# BLDC_v3_p2.net
KiCad netlist of a schematic drawn in Altium Designer
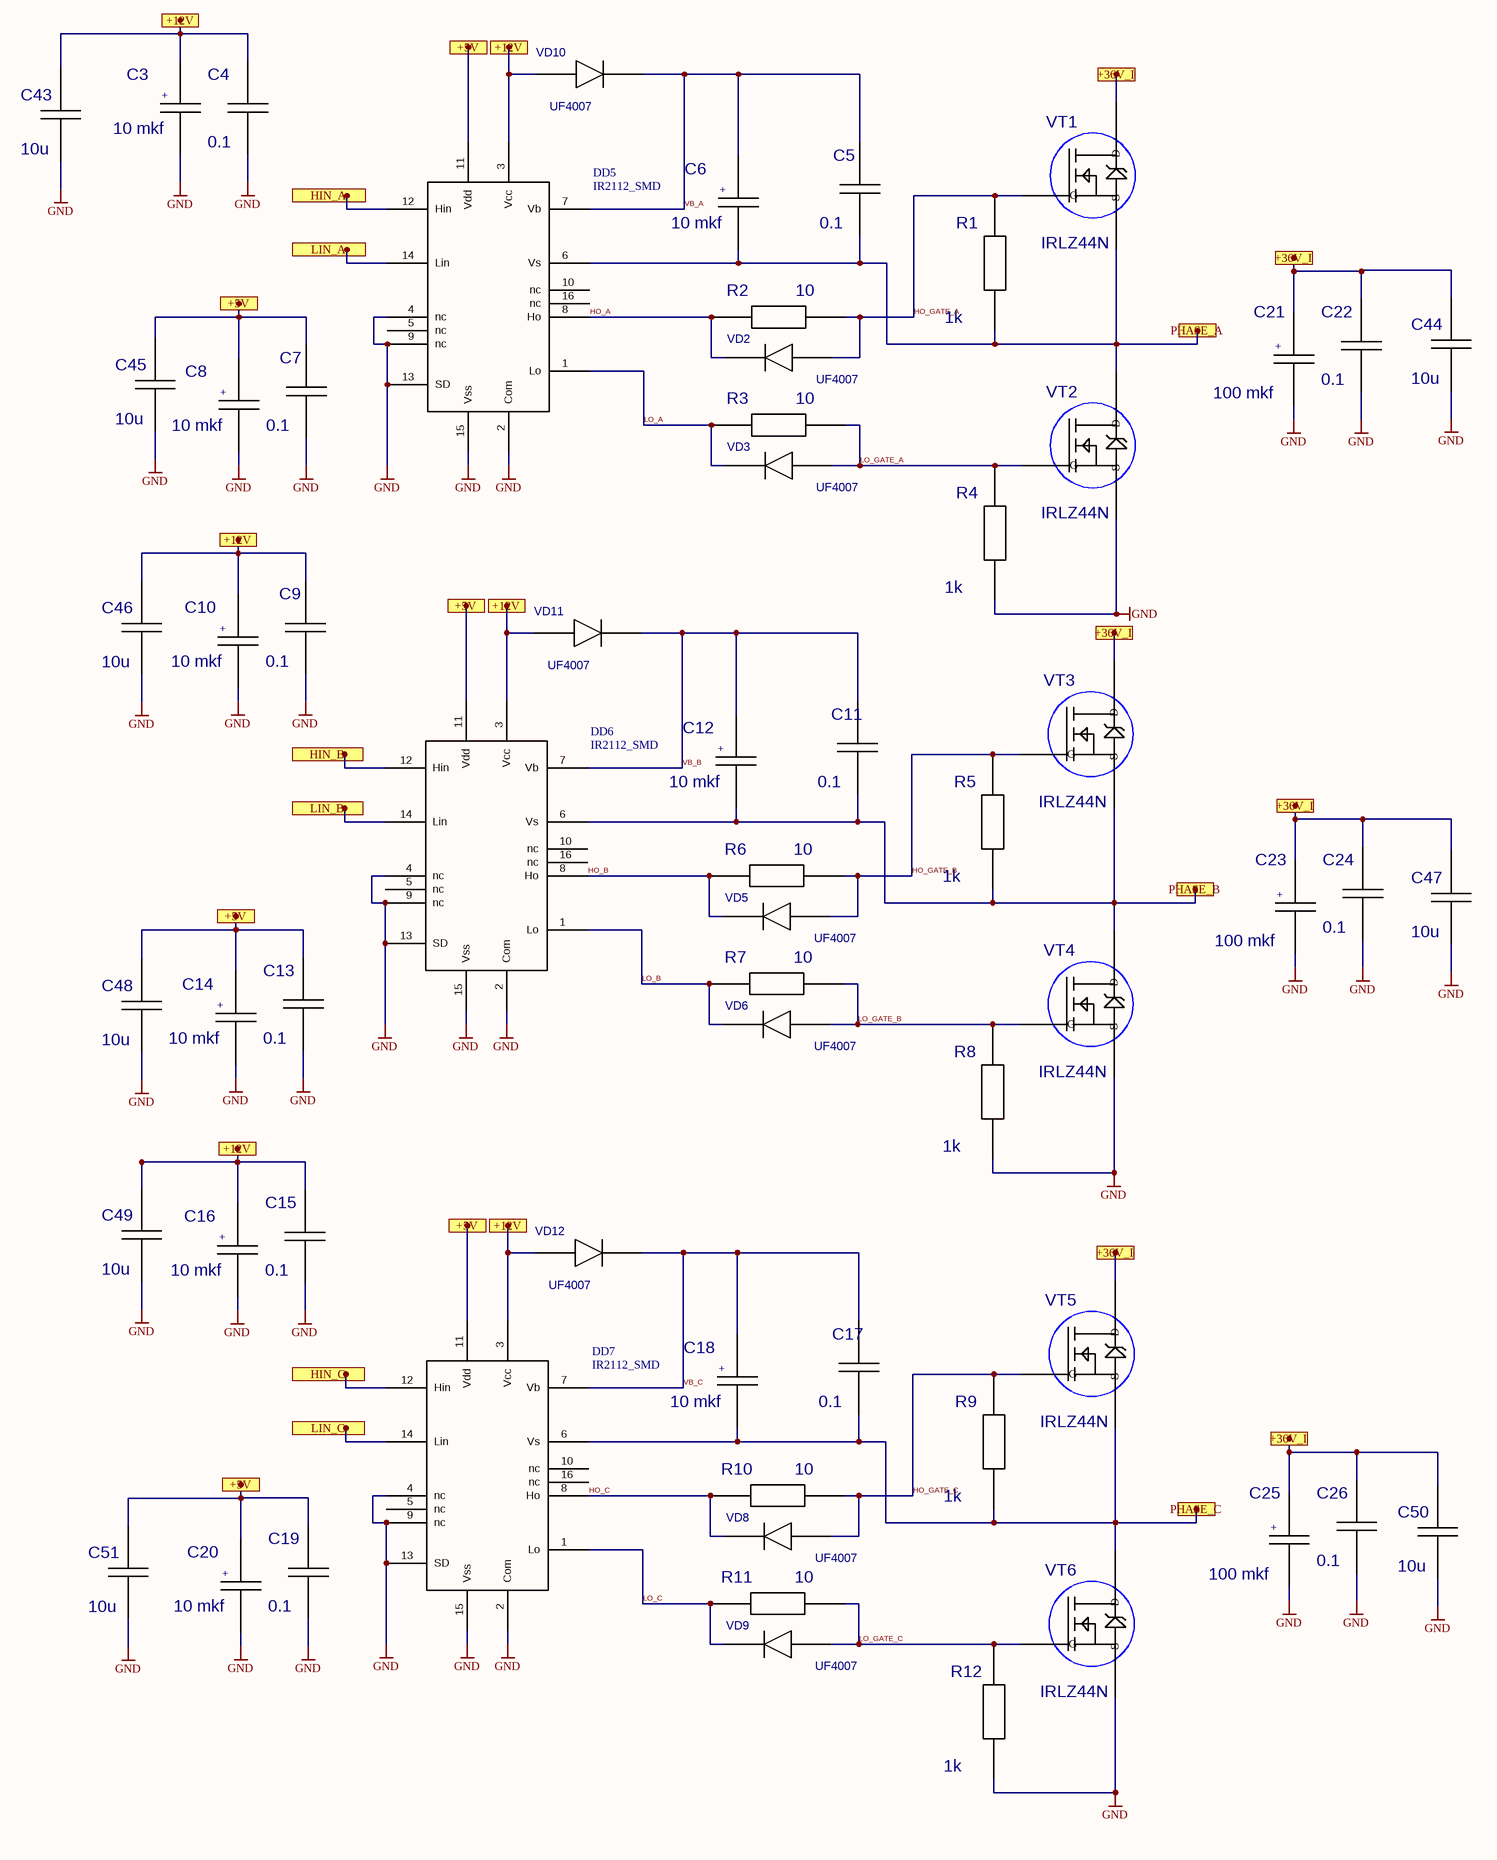
[diagram p0: BLDC_v3_p2.SCHDOC]

(export (version "E")
  (design (tool "Eeschema 10.0.6"))
  (components
    (comp (ref "C3")
      (value "10 mkf")
      (footprint "C10_V")
      (description "C10_V")
      (libsource (lib "") (part "C10_V_3"))
    )
    (comp (ref "C4")
      (value "0.1")
      (footprint "RC1206")
      (description "C_1206")
      (libsource (lib "*") (part "C_1206"))
    )
    (comp (ref "C5")
      (value "0.1")
      (footprint "RC1206")
      (description "C_1206")
      (libsource (lib "") (part "C_1206_1"))
    )
    (comp (ref "C6")
      (value "10 mkf")
      (footprint "C10_V")
      (description "C10_V")
      (libsource (lib "*") (part "C10_V"))
    )
    (comp (ref "C7")
      (value "0.1")
      (footprint "RC1206")
      (description "C_1206")
      (libsource (lib "") (part "C_1206_3"))
    )
    (comp (ref "C8")
      (value "10 mkf")
      (footprint "C10_V")
      (description "C10_V")
      (libsource (lib "") (part "C10_V_4"))
    )
    (comp (ref "C9")
      (value "0.1")
      (footprint "RC1206")
      (description "C_1206")
      (libsource (lib "*") (part "C_1206"))
    )
    (comp (ref "C10")
      (value "10 mkf")
      (footprint "C10_V")
      (description "C10_V")
      (libsource (lib "") (part "C10_V_3"))
    )
    (comp (ref "C11")
      (value "0.1")
      (footprint "RC1206")
      (description "C_1206")
      (libsource (lib "") (part "C_1206_1"))
    )
    (comp (ref "C12")
      (value "10 mkf")
      (footprint "C10_V")
      (description "C10_V")
      (libsource (lib "") (part "C10_V_1"))
    )
    (comp (ref "C13")
      (value "0.1")
      (footprint "RC1206")
      (description "C_1206")
      (libsource (lib "") (part "C_1206_1"))
    )
    (comp (ref "C14")
      (value "10 mkf")
      (footprint "C10_V")
      (description "C10_V")
      (libsource (lib "") (part "C10_V_1"))
    )
    (comp (ref "C15")
      (value "0.1")
      (footprint "RC1206")
      (description "C_1206")
      (libsource (lib "") (part "C_1206_1"))
    )
    (comp (ref "C16")
      (value "10 mkf")
      (footprint "C10_V")
      (description "C10_V")
      (libsource (lib "") (part "C10_V_1"))
    )
    (comp (ref "C17")
      (value "0.1")
      (footprint "RC1206")
      (description "C_1206")
      (libsource (lib "") (part "C_1206_2"))
    )
    (comp (ref "C18")
      (value "10 mkf")
      (footprint "C10_V")
      (description "C10_V")
      (libsource (lib "") (part "C10_V_2"))
    )
    (comp (ref "C19")
      (value "0.1")
      (footprint "RC1206")
      (description "C_1206")
      (libsource (lib "*") (part "C_1206"))
    )
    (comp (ref "C20")
      (value "10 mkf")
      (footprint "C10_V")
      (description "C10_V")
      (libsource (lib "") (part "C10_V_3"))
    )
    (comp (ref "C21")
      (value "100 mkf")
      (footprint "C100_WIDE")
      (description "C100_V_WIDE")
      (libsource (lib "*") (part "C100_V_WIDE"))
    )
    (comp (ref "C22")
      (value "0.1")
      (footprint "RC1206")
      (description "C_1206")
      (libsource (lib "*") (part "C_1206"))
    )
    (comp (ref "C23")
      (value "100 mkf")
      (footprint "C100_WIDE")
      (description "C100_V_WIDE")
      (libsource (lib "*") (part "C100_V_WIDE"))
    )
    (comp (ref "C24")
      (value "0.1")
      (footprint "RC1206")
      (description "C_1206")
      (libsource (lib "*") (part "C_1206"))
    )
    (comp (ref "C25")
      (value "100 mkf")
      (footprint "C100_WIDE")
      (description "C100_V_WIDE")
      (libsource (lib "") (part "C100_V_WIDE_1"))
    )
    (comp (ref "C26")
      (value "0.1")
      (footprint "RC1206")
      (description "C_1206")
      (libsource (lib "") (part "C_1206_1"))
    )
    (comp (ref "C43")
      (value "10u")
      (footprint "RC1206")
      (description "C_1206")
      (libsource (lib "") (part "C_1206_1"))
    )
    (comp (ref "C44")
      (value "10u")
      (footprint "RC1206")
      (description "C_1206")
      (libsource (lib "") (part "C_1206_1"))
    )
    (comp (ref "C45")
      (value "10u")
      (footprint "RC1206")
      (description "C_1206")
      (libsource (lib "") (part "C_1206_1"))
    )
    (comp (ref "C46")
      (value "10u")
      (footprint "RC1206")
      (description "C_1206")
      (libsource (lib "") (part "C_1206_1"))
    )
    (comp (ref "C47")
      (value "10u")
      (footprint "RC1206")
      (description "C_1206")
      (libsource (lib "") (part "C_1206_1"))
    )
    (comp (ref "C48")
      (value "10u")
      (footprint "RC1206")
      (description "C_1206")
      (libsource (lib "") (part "C_1206_1"))
    )
    (comp (ref "C49")
      (value "10u")
      (footprint "RC1206")
      (description "C_1206")
      (libsource (lib "") (part "C_1206_1"))
    )
    (comp (ref "C50")
      (value "10u")
      (footprint "RC1206")
      (description "C_1206")
      (libsource (lib "") (part "C_1206_1"))
    )
    (comp (ref "C51")
      (value "10u")
      (footprint "RC1206")
      (description "C_1206")
      (libsource (lib "") (part "C_1206_1"))
    )
    (comp (ref "DD5")
      (value "IR2112_SMD")
      (footprint "SOIC16_N")
      (description "High and Low Side Driver")
      (fields (field (name "PUBLISHER") "Altium Limited"))
      (libsource (lib "bldc") (part "IR2112_SMD"))
    )
    (comp (ref "DD6")
      (value "IR2112_SMD")
      (footprint "SOIC16_N")
      (description "High and Low Side Driver")
      (fields (field (name "PUBLISHER") "Altium Limited"))
      (libsource (lib "bldc") (part "IR2112_SMD"))
    )
    (comp (ref "DD7")
      (value "IR2112_SMD")
      (footprint "SOIC16_N")
      (description "High and Low Side Driver")
      (fields (field (name "PUBLISHER") "Altium Limited"))
      (libsource (lib "bldc") (part "IR2112_SMD"))
    )
    (comp (ref "R1")
      (value "1k")
      (footprint "CC1206")
      (description "R_1206")
      (libsource (lib "") (part "R_1206_1"))
    )
    (comp (ref "R2")
      (value "10")
      (footprint "CC1206")
      (description "R_1206")
      (libsource (lib "*") (part "R_1206"))
    )
    (comp (ref "R3")
      (value "10")
      (footprint "CC1206")
      (description "R_1206")
      (libsource (lib "") (part "R_1206_2"))
    )
    (comp (ref "R4")
      (value "1k")
      (footprint "CC1206")
      (description "R_1206")
      (libsource (lib "") (part "R_1206_1"))
    )
    (comp (ref "R5")
      (value "1k")
      (footprint "CC1206")
      (description "R_1206")
      (libsource (lib "") (part "R_1206_2"))
    )
    (comp (ref "R6")
      (value "10")
      (footprint "CC1206")
      (description "R_1206")
      (libsource (lib "") (part "R_1206_1"))
    )
    (comp (ref "R7")
      (value "10")
      (footprint "CC1206")
      (description "R_1206")
      (libsource (lib "") (part "R_1206_1"))
    )
    (comp (ref "R8")
      (value "1k")
      (footprint "CC1206")
      (description "R_1206")
      (libsource (lib "") (part "R_1206_2"))
    )
    (comp (ref "R9")
      (value "1k")
      (footprint "CC1206")
      (description "R_1206")
      (libsource (lib "") (part "R_1206_1"))
    )
    (comp (ref "R10")
      (value "10")
      (footprint "CC1206")
      (description "R_1206")
      (libsource (lib "") (part "R_1206_2"))
    )
    (comp (ref "R11")
      (value "10")
      (footprint "CC1206")
      (description "R_1206")
      (libsource (lib "") (part "R_1206_2"))
    )
    (comp (ref "R12")
      (value "1k")
      (footprint "CC1206")
      (description "R_1206")
      (libsource (lib "") (part "R_1206_1"))
    )
    (comp (ref "VD2")
      (value "UF4007")
      (footprint "DIODE_V_WIDE_HOLES")
      (description "DIODE_LIE_WIDE")
      (libsource (lib "*") (part "DIODE_LIE_WIDE"))
    )
    (comp (ref "VD3")
      (value "UF4007")
      (footprint "DIODE_V_WIDE_HOLES")
      (description "DIODE_LIE_WIDE")
      (libsource (lib "*") (part "DIODE_LIE_WIDE"))
    )
    (comp (ref "VD5")
      (value "UF4007")
      (footprint "DIODE_V_WIDE_HOLES")
      (description "DIODE_LIE_WIDE")
      (libsource (lib "*") (part "DIODE_LIE_WIDE"))
    )
    (comp (ref "VD6")
      (value "UF4007")
      (footprint "DIODE_V_WIDE_HOLES")
      (description "DIODE_LIE_WIDE")
      (libsource (lib "*") (part "DIODE_LIE_WIDE"))
    )
    (comp (ref "VD8")
      (value "UF4007")
      (footprint "DIODE_V_WIDE_HOLES")
      (description "DIODE_LIE_WIDE")
      (libsource (lib "*") (part "DIODE_LIE_WIDE"))
    )
    (comp (ref "VD9")
      (value "UF4007")
      (footprint "DIODE_V_WIDE_HOLES")
      (description "DIODE_LIE_WIDE")
      (libsource (lib "*") (part "DIODE_LIE_WIDE"))
    )
    (comp (ref "VD10")
      (value "UF4007")
      (footprint "DIODE_V_WIDE_HOLES")
      (description "DIODE_LIE_WIDE")
      (libsource (lib "*") (part "DIODE_LIE_WIDE"))
    )
    (comp (ref "VD11")
      (value "UF4007")
      (footprint "DIODE_V_WIDE_HOLES")
      (description "DIODE_LIE_WIDE")
      (libsource (lib "*") (part "DIODE_LIE_WIDE"))
    )
    (comp (ref "VD12")
      (value "UF4007")
      (footprint "DIODE_V_WIDE_HOLES")
      (description "DIODE_LIE_WIDE")
      (libsource (lib "*") (part "DIODE_LIE_WIDE"))
    )
    (comp (ref "VT1") (value "IRLZ44N") (footprint "IRLZ44N") (libsource (lib "") (part "IRLZ44N_1")))
    (comp (ref "VT2") (value "IRLZ44N") (footprint "IRLZ44N") (libsource (lib "") (part "IRLZ44N_1")))
    (comp (ref "VT3") (value "IRLZ44N") (footprint "IRLZ44N") (libsource (lib "*") (part "IRLZ44N")))
    (comp (ref "VT4") (value "IRLZ44N") (footprint "IRLZ44N") (libsource (lib "") (part "IRLZ44N_2")))
    (comp (ref "VT5") (value "IRLZ44N") (footprint "IRLZ44N") (libsource (lib "") (part "IRLZ44N_1")))
    (comp (ref "VT6") (value "IRLZ44N") (footprint "IRLZ44N") (libsource (lib "") (part "IRLZ44N_3")))
  )
  (nets
    (net (code "7") (name "/HO_A") (class "Default")
      (node (ref "DD5") (pin "8") (pinfunction "Ho_8") (pintype "passive"))
      (node (ref "R2") (pin "1") (pinfunction "A1_1") (pintype "passive"))
      (node (ref "VD2") (pin "2") (pinfunction "A_2") (pintype "passive"))
    )
    (net (code "8") (name "/HO_B") (class "Default")
      (node (ref "DD6") (pin "8") (pinfunction "Ho_8") (pintype "passive"))
      (node (ref "R6") (pin "1") (pinfunction "A1_1") (pintype "passive"))
      (node (ref "VD5") (pin "2") (pinfunction "A_2") (pintype "passive"))
    )
    (net (code "9") (name "/HO_C") (class "Default")
      (node (ref "DD7") (pin "8") (pinfunction "Ho_8") (pintype "passive"))
      (node (ref "R10") (pin "1") (pinfunction "A1_1") (pintype "passive"))
      (node (ref "VD8") (pin "2") (pinfunction "A_2") (pintype "passive"))
    )
    (net (code "10") (name "/HO_GATE_A") (class "Default")
      (node (ref "R1") (pin "1") (pinfunction "A1_1") (pintype "passive"))
      (node (ref "R2") (pin "2") (pinfunction "A2_2") (pintype "passive"))
      (node (ref "VD2") (pin "1") (pinfunction "C_1") (pintype "passive"))
      (node (ref "VT1") (pin "1") (pinfunction "G_1") (pintype "passive"))
    )
    (net (code "11") (name "/HO_GATE_B") (class "Default")
      (node (ref "R5") (pin "1") (pinfunction "A1_1") (pintype "passive"))
      (node (ref "R6") (pin "2") (pinfunction "A2_2") (pintype "passive"))
      (node (ref "VD5") (pin "1") (pinfunction "C_1") (pintype "passive"))
      (node (ref "VT3") (pin "1") (pinfunction "G_1") (pintype "passive"))
    )
    (net (code "12") (name "/HO_GATE_C") (class "Default")
      (node (ref "R10") (pin "2") (pinfunction "A2_2") (pintype "passive"))
      (node (ref "R9") (pin "1") (pinfunction "A1_1") (pintype "passive"))
      (node (ref "VD8") (pin "1") (pinfunction "C_1") (pintype "passive"))
      (node (ref "VT5") (pin "1") (pinfunction "G_1") (pintype "passive"))
    )
    (net (code "16") (name "/LO_A") (class "Default")
      (node (ref "DD5") (pin "1") (pinfunction "Lo_1") (pintype "passive"))
      (node (ref "R3") (pin "1") (pinfunction "A1_1") (pintype "passive"))
      (node (ref "VD3") (pin "2") (pinfunction "A_2") (pintype "passive"))
    )
    (net (code "17") (name "/LO_B") (class "Default")
      (node (ref "DD6") (pin "1") (pinfunction "Lo_1") (pintype "passive"))
      (node (ref "R7") (pin "1") (pinfunction "A1_1") (pintype "passive"))
      (node (ref "VD6") (pin "2") (pinfunction "A_2") (pintype "passive"))
    )
    (net (code "18") (name "/LO_C") (class "Default")
      (node (ref "DD7") (pin "1") (pinfunction "Lo_1") (pintype "passive"))
      (node (ref "R11") (pin "1") (pinfunction "A1_1") (pintype "passive"))
      (node (ref "VD9") (pin "2") (pinfunction "A_2") (pintype "passive"))
    )
    (net (code "19") (name "/LO_GATE_A") (class "Default")
      (node (ref "R3") (pin "2") (pinfunction "A2_2") (pintype "passive"))
      (node (ref "R4") (pin "1") (pinfunction "A1_1") (pintype "passive"))
      (node (ref "VD3") (pin "1") (pinfunction "C_1") (pintype "passive"))
      (node (ref "VT2") (pin "1") (pinfunction "G_1") (pintype "passive"))
    )
    (net (code "20") (name "/LO_GATE_B") (class "Default")
      (node (ref "R7") (pin "2") (pinfunction "A2_2") (pintype "passive"))
      (node (ref "R8") (pin "1") (pinfunction "A1_1") (pintype "passive"))
      (node (ref "VD6") (pin "1") (pinfunction "C_1") (pintype "passive"))
      (node (ref "VT4") (pin "1") (pinfunction "G_1") (pintype "passive"))
    )
    (net (code "21") (name "/LO_GATE_C") (class "Default")
      (node (ref "R11") (pin "2") (pinfunction "A2_2") (pintype "passive"))
      (node (ref "R12") (pin "1") (pinfunction "A1_1") (pintype "passive"))
      (node (ref "VD9") (pin "1") (pinfunction "C_1") (pintype "passive"))
      (node (ref "VT6") (pin "1") (pinfunction "G_1") (pintype "passive"))
    )
    (net (code "25") (name "/VB_A") (class "Default")
      (node (ref "C5") (pin "2") (pinfunction "A2_2") (pintype "passive"))
      (node (ref "C6") (pin "1") (pinfunction "A2_1") (pintype "passive"))
      (node (ref "DD5") (pin "7") (pinfunction "Vb_7") (pintype "passive"))
      (node (ref "VD10") (pin "2") (pinfunction "A_2") (pintype "passive"))
    )
    (net (code "26") (name "/VB_B") (class "Default")
      (node (ref "C11") (pin "2") (pinfunction "A2_2") (pintype "passive"))
      (node (ref "C12") (pin "1") (pinfunction "A2_1") (pintype "passive"))
      (node (ref "DD6") (pin "7") (pinfunction "Vb_7") (pintype "passive"))
      (node (ref "VD11") (pin "2") (pinfunction "A_2") (pintype "passive"))
    )
    (net (code "27") (name "/VB_C") (class "Default")
      (node (ref "C17") (pin "2") (pinfunction "A2_2") (pintype "passive"))
      (node (ref "C18") (pin "1") (pinfunction "A2_1") (pintype "passive"))
      (node (ref "DD7") (pin "7") (pinfunction "Vb_7") (pintype "passive"))
      (node (ref "VD12") (pin "2") (pinfunction "A_2") (pintype "passive"))
    )
    (net (code "28") (name "GND") (class "Default")
      (node (ref "C10") (pin "2") (pinfunction "A1_2") (pintype "passive"))
      (node (ref "C13") (pin "1") (pinfunction "A1_1") (pintype "passive"))
      (node (ref "C14") (pin "2") (pinfunction "A1_2") (pintype "passive"))
      (node (ref "C15") (pin "1") (pinfunction "A1_1") (pintype "passive"))
      (node (ref "C16") (pin "2") (pinfunction "A1_2") (pintype "passive"))
      (node (ref "C19") (pin "1") (pinfunction "A1_1") (pintype "passive"))
      (node (ref "C20") (pin "2") (pinfunction "A1_2") (pintype "passive"))
      (node (ref "C21") (pin "2") (pinfunction "A1_2") (pintype "passive"))
      (node (ref "C22") (pin "1") (pinfunction "A1_1") (pintype "passive"))
      (node (ref "C23") (pin "2") (pinfunction "A1_2") (pintype "passive"))
      (node (ref "C24") (pin "1") (pinfunction "A1_1") (pintype "passive"))
      (node (ref "C25") (pin "2") (pinfunction "A1_2") (pintype "passive"))
      (node (ref "C26") (pin "1") (pinfunction "A1_1") (pintype "passive"))
      (node (ref "C3") (pin "2") (pinfunction "A1_2") (pintype "passive"))
      (node (ref "C4") (pin "1") (pinfunction "A1_1") (pintype "passive"))
      (node (ref "C43") (pin "1") (pinfunction "A1_1") (pintype "passive"))
      (node (ref "C44") (pin "1") (pinfunction "A1_1") (pintype "passive"))
      (node (ref "C45") (pin "1") (pinfunction "A1_1") (pintype "passive"))
      (node (ref "C46") (pin "1") (pinfunction "A1_1") (pintype "passive"))
      (node (ref "C47") (pin "1") (pinfunction "A1_1") (pintype "passive"))
      (node (ref "C48") (pin "1") (pinfunction "A1_1") (pintype "passive"))
      (node (ref "C49") (pin "1") (pinfunction "A1_1") (pintype "passive"))
      (node (ref "C50") (pin "1") (pinfunction "A1_1") (pintype "passive"))
      (node (ref "C51") (pin "1") (pinfunction "A1_1") (pintype "passive"))
      (node (ref "C7") (pin "1") (pinfunction "A1_1") (pintype "passive"))
      (node (ref "C8") (pin "2") (pinfunction "A1_2") (pintype "passive"))
      (node (ref "C9") (pin "1") (pinfunction "A1_1") (pintype "passive"))
      (node (ref "DD5") (pin "13") (pinfunction "SD_13") (pintype "passive"))
      (node (ref "DD5") (pin "15") (pinfunction "Vss_15") (pintype "passive"))
      (node (ref "DD5") (pin "2") (pinfunction "Com_2") (pintype "passive"))
      (node (ref "DD5") (pin "4") (pinfunction "nc_4") (pintype "passive"))
      (node (ref "DD5") (pin "9") (pinfunction "nc_9") (pintype "passive"))
      (node (ref "DD6") (pin "13") (pinfunction "SD_13") (pintype "passive"))
      (node (ref "DD6") (pin "15") (pinfunction "Vss_15") (pintype "passive"))
      (node (ref "DD6") (pin "2") (pinfunction "Com_2") (pintype "passive"))
      (node (ref "DD6") (pin "4") (pinfunction "nc_4") (pintype "passive"))
      (node (ref "DD6") (pin "9") (pinfunction "nc_9") (pintype "passive"))
      (node (ref "DD7") (pin "13") (pinfunction "SD_13") (pintype "passive"))
      (node (ref "DD7") (pin "15") (pinfunction "Vss_15") (pintype "passive"))
      (node (ref "DD7") (pin "2") (pinfunction "Com_2") (pintype "passive"))
      (node (ref "DD7") (pin "4") (pinfunction "nc_4") (pintype "passive"))
      (node (ref "DD7") (pin "9") (pinfunction "nc_9") (pintype "passive"))
      (node (ref "R12") (pin "2") (pinfunction "A2_2") (pintype "passive"))
      (node (ref "R4") (pin "2") (pinfunction "A2_2") (pintype "passive"))
      (node (ref "R8") (pin "2") (pinfunction "A2_2") (pintype "passive"))
      (node (ref "VT2") (pin "3") (pinfunction "S_3") (pintype "passive"))
      (node (ref "VT4") (pin "3") (pinfunction "S_3") (pintype "passive"))
      (node (ref "VT6") (pin "3") (pinfunction "S_3") (pintype "passive"))
    )
    (net (code "29") (name "Net-(C3-A2)") (class "Default")
      (node (ref "C3") (pin "1") (pinfunction "A2_1") (pintype "passive"))
      (node (ref "C4") (pin "2") (pinfunction "A2_2") (pintype "passive"))
      (node (ref "C43") (pin "2") (pinfunction "A2_2") (pintype "passive"))
    )
    (net (code "30") (name "Net-(C5-A1)") (class "Default")
      (node (ref "C5") (pin "1") (pinfunction "A1_1") (pintype "passive"))
      (node (ref "C6") (pin "2") (pinfunction "A1_2") (pintype "passive"))
      (node (ref "DD5") (pin "6") (pinfunction "Vs_6") (pintype "passive"))
      (node (ref "R1") (pin "2") (pinfunction "A2_2") (pintype "passive"))
      (node (ref "VT1") (pin "3") (pinfunction "S_3") (pintype "passive"))
      (node (ref "VT2") (pin "2") (pinfunction "D_2") (pintype "passive"))
    )
    (net (code "31") (name "Net-(C10-A2)") (class "Default")
      (node (ref "C10") (pin "1") (pinfunction "A2_1") (pintype "passive"))
      (node (ref "C46") (pin "2") (pinfunction "A2_2") (pintype "passive"))
      (node (ref "C9") (pin "2") (pinfunction "A2_2") (pintype "passive"))
    )
    (net (code "32") (name "Net-(C11-A1)") (class "Default")
      (node (ref "C11") (pin "1") (pinfunction "A1_1") (pintype "passive"))
      (node (ref "C12") (pin "2") (pinfunction "A1_2") (pintype "passive"))
      (node (ref "DD6") (pin "6") (pinfunction "Vs_6") (pintype "passive"))
      (node (ref "R5") (pin "2") (pinfunction "A2_2") (pintype "passive"))
      (node (ref "VT3") (pin "3") (pinfunction "S_3") (pintype "passive"))
      (node (ref "VT4") (pin "2") (pinfunction "D_2") (pintype "passive"))
    )
    (net (code "33") (name "Net-(C13-A2)") (class "Default")
      (node (ref "C13") (pin "2") (pinfunction "A2_2") (pintype "passive"))
      (node (ref "C14") (pin "1") (pinfunction "A2_1") (pintype "passive"))
      (node (ref "C48") (pin "2") (pinfunction "A2_2") (pintype "passive"))
    )
    (net (code "34") (name "Net-(C15-A2)") (class "Default")
      (node (ref "C15") (pin "2") (pinfunction "A2_2") (pintype "passive"))
      (node (ref "C16") (pin "1") (pinfunction "A2_1") (pintype "passive"))
      (node (ref "C49") (pin "2") (pinfunction "A2_2") (pintype "passive"))
    )
    (net (code "35") (name "Net-(C17-A1)") (class "Default")
      (node (ref "C17") (pin "1") (pinfunction "A1_1") (pintype "passive"))
      (node (ref "C18") (pin "2") (pinfunction "A1_2") (pintype "passive"))
      (node (ref "DD7") (pin "6") (pinfunction "Vs_6") (pintype "passive"))
      (node (ref "R9") (pin "2") (pinfunction "A2_2") (pintype "passive"))
      (node (ref "VT5") (pin "3") (pinfunction "S_3") (pintype "passive"))
      (node (ref "VT6") (pin "2") (pinfunction "D_2") (pintype "passive"))
    )
    (net (code "36") (name "Net-(C19-A2)") (class "Default")
      (node (ref "C19") (pin "2") (pinfunction "A2_2") (pintype "passive"))
      (node (ref "C20") (pin "1") (pinfunction "A2_1") (pintype "passive"))
      (node (ref "C51") (pin "2") (pinfunction "A2_2") (pintype "passive"))
    )
    (net (code "37") (name "Net-(C21-A2)") (class "Default")
      (node (ref "C21") (pin "1") (pinfunction "A2_1") (pintype "passive"))
      (node (ref "C22") (pin "2") (pinfunction "A2_2") (pintype "passive"))
      (node (ref "C44") (pin "2") (pinfunction "A2_2") (pintype "passive"))
    )
    (net (code "38") (name "Net-(C23-A2)") (class "Default")
      (node (ref "C23") (pin "1") (pinfunction "A2_1") (pintype "passive"))
      (node (ref "C24") (pin "2") (pinfunction "A2_2") (pintype "passive"))
      (node (ref "C47") (pin "2") (pinfunction "A2_2") (pintype "passive"))
    )
    (net (code "39") (name "Net-(C25-A2)") (class "Default")
      (node (ref "C25") (pin "1") (pinfunction "A2_1") (pintype "passive"))
      (node (ref "C26") (pin "2") (pinfunction "A2_2") (pintype "passive"))
      (node (ref "C50") (pin "2") (pinfunction "A2_2") (pintype "passive"))
    )
    (net (code "40") (name "Net-(C45-A2)") (class "Default")
      (node (ref "C45") (pin "2") (pinfunction "A2_2") (pintype "passive"))
      (node (ref "C7") (pin "2") (pinfunction "A2_2") (pintype "passive"))
      (node (ref "C8") (pin "1") (pinfunction "A2_1") (pintype "passive"))
    )
    (net (code "41") (name "Net-(DD5-Vcc)") (class "Default")
      (node (ref "DD5") (pin "3") (pinfunction "Vcc_3") (pintype "passive"))
      (node (ref "VD10") (pin "1") (pinfunction "C_1") (pintype "passive"))
    )
    (net (code "42") (name "Net-(DD6-Vcc)") (class "Default")
      (node (ref "DD6") (pin "3") (pinfunction "Vcc_3") (pintype "passive"))
      (node (ref "VD11") (pin "1") (pinfunction "C_1") (pintype "passive"))
    )
    (net (code "43") (name "Net-(DD7-Vcc)") (class "Default")
      (node (ref "DD7") (pin "3") (pinfunction "Vcc_3") (pintype "passive"))
      (node (ref "VD12") (pin "1") (pinfunction "C_1") (pintype "passive"))
    )
    (net (code "44") (name "unconnected-(DD5-Hin-Pad12)") (class "Default")
      (node (ref "DD5") (pin "12") (pinfunction "Hin_12") (pintype "passive"))
    )
    (net (code "45") (name "unconnected-(DD5-Lin-Pad14)") (class "Default")
      (node (ref "DD5") (pin "14") (pinfunction "Lin_14") (pintype "passive"))
    )
    (net (code "46") (name "unconnected-(DD5-Vdd-Pad11)") (class "Default")
      (node (ref "DD5") (pin "11") (pinfunction "Vdd_11") (pintype "passive"))
    )
    (net (code "47") (name "unconnected-(DD5-nc-Pad5)") (class "Default")
      (node (ref "DD5") (pin "5") (pinfunction "nc_5") (pintype "passive"))
    )
    (net (code "48") (name "unconnected-(DD5-nc-Pad10)") (class "Default")
      (node (ref "DD5") (pin "10") (pinfunction "nc_10") (pintype "passive"))
    )
    (net (code "49") (name "unconnected-(DD5-nc-Pad16)") (class "Default")
      (node (ref "DD5") (pin "16") (pinfunction "nc_16") (pintype "passive"))
    )
    (net (code "50") (name "unconnected-(DD6-Hin-Pad12)") (class "Default")
      (node (ref "DD6") (pin "12") (pinfunction "Hin_12") (pintype "passive"))
    )
    (net (code "51") (name "unconnected-(DD6-Lin-Pad14)") (class "Default")
      (node (ref "DD6") (pin "14") (pinfunction "Lin_14") (pintype "passive"))
    )
    (net (code "52") (name "unconnected-(DD6-Vdd-Pad11)") (class "Default")
      (node (ref "DD6") (pin "11") (pinfunction "Vdd_11") (pintype "passive"))
    )
    (net (code "53") (name "unconnected-(DD6-nc-Pad5)") (class "Default")
      (node (ref "DD6") (pin "5") (pinfunction "nc_5") (pintype "passive"))
    )
    (net (code "54") (name "unconnected-(DD6-nc-Pad10)") (class "Default")
      (node (ref "DD6") (pin "10") (pinfunction "nc_10") (pintype "passive"))
    )
    (net (code "55") (name "unconnected-(DD6-nc-Pad16)") (class "Default")
      (node (ref "DD6") (pin "16") (pinfunction "nc_16") (pintype "passive"))
    )
    (net (code "56") (name "unconnected-(DD7-Hin-Pad12)") (class "Default")
      (node (ref "DD7") (pin "12") (pinfunction "Hin_12") (pintype "passive"))
    )
    (net (code "57") (name "unconnected-(DD7-Lin-Pad14)") (class "Default")
      (node (ref "DD7") (pin "14") (pinfunction "Lin_14") (pintype "passive"))
    )
    (net (code "58") (name "unconnected-(DD7-Vdd-Pad11)") (class "Default")
      (node (ref "DD7") (pin "11") (pinfunction "Vdd_11") (pintype "passive"))
    )
    (net (code "59") (name "unconnected-(DD7-nc-Pad5)") (class "Default")
      (node (ref "DD7") (pin "5") (pinfunction "nc_5") (pintype "passive"))
    )
    (net (code "60") (name "unconnected-(DD7-nc-Pad10)") (class "Default")
      (node (ref "DD7") (pin "10") (pinfunction "nc_10") (pintype "passive"))
    )
    (net (code "61") (name "unconnected-(DD7-nc-Pad16)") (class "Default")
      (node (ref "DD7") (pin "16") (pinfunction "nc_16") (pintype "passive"))
    )
    (net (code "62") (name "unconnected-(VT1-D-Pad2)") (class "Default")
      (node (ref "VT1") (pin "2") (pinfunction "D_2") (pintype "passive"))
    )
    (net (code "63") (name "unconnected-(VT3-D-Pad2)") (class "Default")
      (node (ref "VT3") (pin "2") (pinfunction "D_2") (pintype "passive"))
    )
    (net (code "64") (name "unconnected-(VT5-D-Pad2)") (class "Default")
      (node (ref "VT5") (pin "2") (pinfunction "D_2") (pintype "passive"))
    )
  )
)
